# uNavMasterBoard.net
KiCad netlist of a schematic drawn in EAGLE
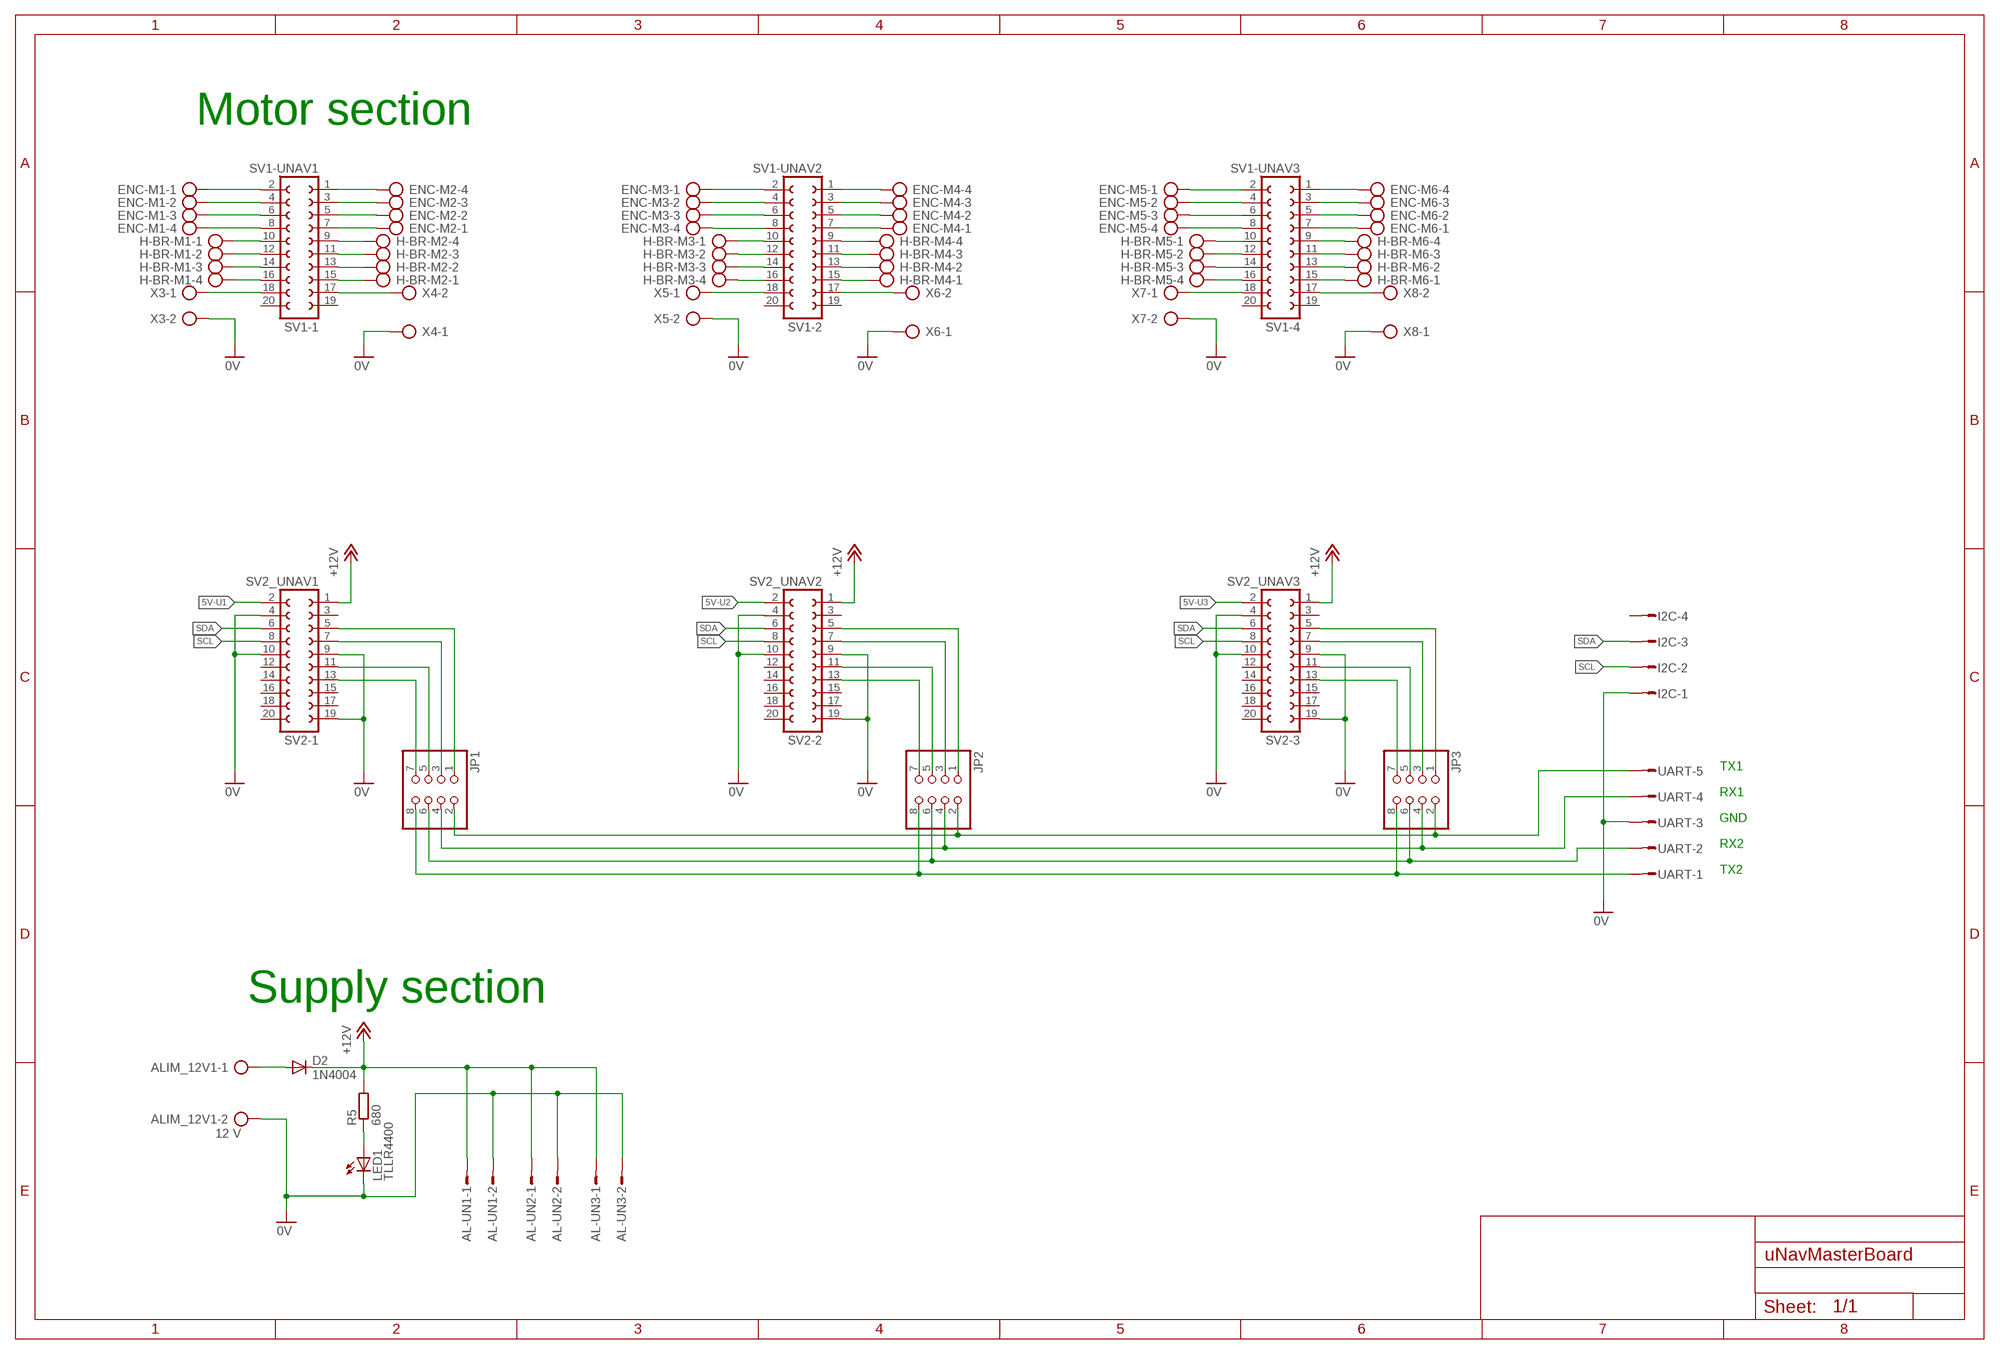
[diagram p0: schematic, sheet 1]

(export (version "E")
  (design (tool "Eeschema 10.0.6"))
  (components
    (comp (ref "AL-UN1")
      (value "S02P")
      (footprint "eagle-import:S02P")
      (fields (field (name "OC_FARNELL") "unknown") (field (name "OC_NEWARK") "unknown"))
      (libsource (lib "eagle-import") (part "S02P"))
    )
    (comp (ref "AL-UN2")
      (value "S02P")
      (footprint "eagle-import:S02P")
      (fields (field (name "OC_FARNELL") "unknown") (field (name "OC_NEWARK") "unknown"))
      (libsource (lib "eagle-import") (part "S02P"))
    )
    (comp (ref "AL-UN3")
      (value "S02P")
      (footprint "eagle-import:S02P")
      (fields (field (name "OC_FARNELL") "unknown") (field (name "OC_NEWARK") "unknown"))
      (libsource (lib "eagle-import") (part "S02P"))
    )
    (comp (ref "ALIM_12V1")
      (value "12 V")
      (footprint "eagle-import:AK500_2")
      (fields (field (name "OC_FARNELL") "unknown") (field (name "OC_NEWARK") "unknown"))
      (libsource (lib "eagle-import") (part "AK500/2"))
    )
    (comp (ref "D2")
      (value "1N4004")
      (footprint "eagle-import:DO41-10")
      (libsource (lib "eagle-import") (part "1N4004"))
    )
    (comp (ref "ENC-M1")
      (value "AK500/4")
      (footprint "eagle-import:AK500_4")
      (libsource (lib "eagle-import") (part "AK500/4"))
    )
    (comp (ref "ENC-M2")
      (value "AK500/4")
      (footprint "eagle-import:AK500_4")
      (libsource (lib "eagle-import") (part "AK500/4"))
    )
    (comp (ref "ENC-M3")
      (value "AK500/4")
      (footprint "eagle-import:AK500_4")
      (libsource (lib "eagle-import") (part "AK500/4"))
    )
    (comp (ref "ENC-M4")
      (value "AK500/4")
      (footprint "eagle-import:AK500_4")
      (libsource (lib "eagle-import") (part "AK500/4"))
    )
    (comp (ref "ENC-M5")
      (value "AK500/4")
      (footprint "eagle-import:AK500_4")
      (libsource (lib "eagle-import") (part "AK500/4"))
    )
    (comp (ref "ENC-M6")
      (value "AK500/4")
      (footprint "eagle-import:AK500_4")
      (libsource (lib "eagle-import") (part "AK500/4"))
    )
    (comp (ref "H-BR-M1")
      (value "AK500/4")
      (footprint "eagle-import:AK500_4")
      (libsource (lib "eagle-import") (part "AK500/4"))
    )
    (comp (ref "H-BR-M2")
      (value "AK500/4")
      (footprint "eagle-import:AK500_4")
      (libsource (lib "eagle-import") (part "AK500/4"))
    )
    (comp (ref "H-BR-M3")
      (value "AK500/4")
      (footprint "eagle-import:AK500_4")
      (libsource (lib "eagle-import") (part "AK500/4"))
    )
    (comp (ref "H-BR-M4")
      (value "AK500/4")
      (footprint "eagle-import:AK500_4")
      (libsource (lib "eagle-import") (part "AK500/4"))
    )
    (comp (ref "H-BR-M5")
      (value "AK500/4")
      (footprint "eagle-import:AK500_4")
      (libsource (lib "eagle-import") (part "AK500/4"))
    )
    (comp (ref "H-BR-M6")
      (value "AK500/4")
      (footprint "eagle-import:AK500_4")
      (libsource (lib "eagle-import") (part "AK500/4"))
    )
    (comp (ref "I2C")
      (value "S04P")
      (footprint "eagle-import:S04P")
      (libsource (lib "eagle-import") (part "S04P"))
    )
    (comp (ref "JP1")
      (value "PINHD-2X4")
      (footprint "eagle-import:2X04")
      (libsource (lib "eagle-import") (part "PINHD-2X4"))
    )
    (comp (ref "JP2")
      (value "PINHD-2X4")
      (footprint "eagle-import:2X04")
      (libsource (lib "eagle-import") (part "PINHD-2X4"))
    )
    (comp (ref "JP3")
      (value "PINHD-2X4")
      (footprint "eagle-import:2X04")
      (libsource (lib "eagle-import") (part "PINHD-2X4"))
    )
    (comp (ref "LED1")
      (value "TLLR4400")
      (footprint "eagle-import:LED3MM")
      (fields
        (field (name "MF") "VISHAY SEMICONDUCTOR")
        (field (name "MF_1") "VISHAY SEMICONDUCTOR")
        (field (name "OC_FARNELL") "1612437")
      )
      (libsource (lib "eagle-import") (part "TLLR4400"))
    )
    (comp (ref "R5")
      (value "680")
      (footprint "eagle-import:0207_10")
      (libsource (lib "eagle-import") (part "R-EU_0207/10"))
    )
    (comp (ref "SV1-1")
      (value "SV1-UNAV1")
      (footprint "eagle-import:FE10-2")
      (fields (field (name "OC_FARNELL") "unknown") (field (name "OC_NEWARK") "unknown"))
      (libsource (lib "eagle-import") (part "FE10-2"))
    )
    (comp (ref "SV1-2")
      (value "SV1-UNAV2")
      (footprint "eagle-import:FE10-2")
      (fields (field (name "OC_FARNELL") "unknown") (field (name "OC_NEWARK") "unknown"))
      (libsource (lib "eagle-import") (part "FE10-2"))
    )
    (comp (ref "SV1-4")
      (value "SV1-UNAV3")
      (footprint "eagle-import:FE10-2")
      (fields (field (name "OC_FARNELL") "unknown") (field (name "OC_NEWARK") "unknown"))
      (libsource (lib "eagle-import") (part "FE10-2"))
    )
    (comp (ref "SV2-1")
      (value "SV2_UNAV1")
      (footprint "eagle-import:FE10-2")
      (fields (field (name "OC_FARNELL") "unknown") (field (name "OC_NEWARK") "unknown"))
      (libsource (lib "eagle-import") (part "FE10-2"))
    )
    (comp (ref "SV2-2")
      (value "SV2_UNAV2")
      (footprint "eagle-import:FE10-2")
      (fields (field (name "OC_FARNELL") "unknown") (field (name "OC_NEWARK") "unknown"))
      (libsource (lib "eagle-import") (part "FE10-2"))
    )
    (comp (ref "SV2-3")
      (value "SV2_UNAV3")
      (footprint "eagle-import:FE10-2")
      (fields (field (name "OC_FARNELL") "unknown") (field (name "OC_NEWARK") "unknown"))
      (libsource (lib "eagle-import") (part "FE10-2"))
    )
    (comp (ref "UART")
      (value "S05P")
      (footprint "eagle-import:S05P")
      (libsource (lib "eagle-import") (part "S05P"))
    )
    (comp (ref "X3")
      (value "AK500/2")
      (footprint "eagle-import:AK500_2")
      (libsource (lib "eagle-import") (part "AK500/2"))
    )
    (comp (ref "X4")
      (value "AK500/2")
      (footprint "eagle-import:AK500_2")
      (libsource (lib "eagle-import") (part "AK500/2"))
    )
    (comp (ref "X5")
      (value "AK500/2")
      (footprint "eagle-import:AK500_2")
      (libsource (lib "eagle-import") (part "AK500/2"))
    )
    (comp (ref "X6")
      (value "AK500/2")
      (footprint "eagle-import:AK500_2")
      (libsource (lib "eagle-import") (part "AK500/2"))
    )
    (comp (ref "X7")
      (value "AK500/2")
      (footprint "eagle-import:AK500_2")
      (libsource (lib "eagle-import") (part "AK500/2"))
    )
    (comp (ref "X8")
      (value "AK500/2")
      (footprint "eagle-import:AK500_2")
      (libsource (lib "eagle-import") (part "AK500/2"))
    )
  )
  (nets
    (net (code "1") (name "+12V") (class "Default")
      (node (ref "AL-UN1") (pin "1") (pinfunction "S_1") (pintype "passive"))
      (node (ref "AL-UN2") (pin "1") (pinfunction "S_1") (pintype "passive"))
      (node (ref "AL-UN3") (pin "1") (pinfunction "S_1") (pintype "passive"))
      (node (ref "D2") (pin "C") (pinfunction "C_C") (pintype "passive"))
      (node (ref "R5") (pin "2") (pinfunction "2_2") (pintype "passive"))
      (node (ref "SV2-1") (pin "1") (pinfunction "1_1") (pintype "passive"))
      (node (ref "SV2-2") (pin "1") (pinfunction "1_1") (pintype "passive"))
      (node (ref "SV2-3") (pin "1") (pinfunction "1_1") (pintype "passive"))
    )
    (net (code "2") (name "0V") (class "Default")
      (node (ref "AL-UN1") (pin "2") (pinfunction "S_2") (pintype "passive"))
      (node (ref "AL-UN2") (pin "2") (pinfunction "S_2") (pintype "passive"))
      (node (ref "AL-UN3") (pin "2") (pinfunction "S_2") (pintype "passive"))
      (node (ref "ALIM_12V1") (pin "2") (pinfunction "KL_2") (pintype "passive"))
      (node (ref "I2C") (pin "1") (pinfunction "S_1") (pintype "passive"))
      (node (ref "LED1") (pin "K") (pinfunction "C_K") (pintype "passive"))
      (node (ref "SV2-1") (pin "10") (pinfunction "10_10") (pintype "passive"))
      (node (ref "SV2-1") (pin "19") (pinfunction "19_19") (pintype "passive"))
      (node (ref "SV2-1") (pin "4") (pinfunction "4_4") (pintype "passive"))
      (node (ref "SV2-1") (pin "9") (pinfunction "9_9") (pintype "passive"))
      (node (ref "SV2-2") (pin "10") (pinfunction "10_10") (pintype "passive"))
      (node (ref "SV2-2") (pin "19") (pinfunction "19_19") (pintype "passive"))
      (node (ref "SV2-2") (pin "4") (pinfunction "4_4") (pintype "passive"))
      (node (ref "SV2-2") (pin "9") (pinfunction "9_9") (pintype "passive"))
      (node (ref "SV2-3") (pin "10") (pinfunction "10_10") (pintype "passive"))
      (node (ref "SV2-3") (pin "19") (pinfunction "19_19") (pintype "passive"))
      (node (ref "SV2-3") (pin "4") (pinfunction "4_4") (pintype "passive"))
      (node (ref "SV2-3") (pin "9") (pinfunction "9_9") (pintype "passive"))
      (node (ref "UART") (pin "3") (pinfunction "S_3") (pintype "passive"))
      (node (ref "X3") (pin "2") (pinfunction "KL_2") (pintype "passive"))
      (node (ref "X4") (pin "1") (pinfunction "KL_1") (pintype "passive"))
      (node (ref "X5") (pin "2") (pinfunction "KL_2") (pintype "passive"))
      (node (ref "X6") (pin "1") (pinfunction "KL_1") (pintype "passive"))
      (node (ref "X7") (pin "2") (pinfunction "KL_2") (pintype "passive"))
      (node (ref "X8") (pin "1") (pinfunction "KL_1") (pintype "passive"))
    )
    (net (code "3") (name "5V-U1") (class "Default")
      (node (ref "SV2-1") (pin "2") (pinfunction "2_2") (pintype "passive"))
    )
    (net (code "4") (name "5V-U2") (class "Default")
      (node (ref "SV2-2") (pin "2") (pinfunction "2_2") (pintype "passive"))
    )
    (net (code "5") (name "5V-U3") (class "Default")
      (node (ref "SV2-3") (pin "2") (pinfunction "2_2") (pintype "passive"))
    )
    (net (code "6") (name "Net-(ALIM_12V1A-KL)") (class "Default")
      (node (ref "ALIM_12V1") (pin "1") (pinfunction "KL_1") (pintype "passive"))
      (node (ref "D2") (pin "A") (pinfunction "A_A") (pintype "passive"))
    )
    (net (code "7") (name "Net-(ENC-M1A-KL)") (class "Default")
      (node (ref "ENC-M1") (pin "1") (pinfunction "KL_1") (pintype "passive"))
      (node (ref "SV1-1") (pin "2") (pinfunction "2_2") (pintype "passive"))
    )
    (net (code "8") (name "Net-(ENC-M1B-KL)") (class "Default")
      (node (ref "ENC-M1") (pin "2") (pinfunction "KL_2") (pintype "passive"))
      (node (ref "SV1-1") (pin "4") (pinfunction "4_4") (pintype "passive"))
    )
    (net (code "9") (name "Net-(ENC-M1C-KL)") (class "Default")
      (node (ref "ENC-M1") (pin "3") (pinfunction "KL_3") (pintype "passive"))
      (node (ref "SV1-1") (pin "6") (pinfunction "6_6") (pintype "passive"))
    )
    (net (code "10") (name "Net-(ENC-M1D-KL)") (class "Default")
      (node (ref "ENC-M1") (pin "4") (pinfunction "KL_4") (pintype "passive"))
      (node (ref "SV1-1") (pin "8") (pinfunction "8_8") (pintype "passive"))
    )
    (net (code "11") (name "Net-(ENC-M2A-KL)") (class "Default")
      (node (ref "ENC-M2") (pin "1") (pinfunction "KL_1") (pintype "passive"))
      (node (ref "SV1-1") (pin "7") (pinfunction "7_7") (pintype "passive"))
    )
    (net (code "12") (name "Net-(ENC-M2B-KL)") (class "Default")
      (node (ref "ENC-M2") (pin "2") (pinfunction "KL_2") (pintype "passive"))
      (node (ref "SV1-1") (pin "5") (pinfunction "5_5") (pintype "passive"))
    )
    (net (code "13") (name "Net-(ENC-M2C-KL)") (class "Default")
      (node (ref "ENC-M2") (pin "3") (pinfunction "KL_3") (pintype "passive"))
      (node (ref "SV1-1") (pin "3") (pinfunction "3_3") (pintype "passive"))
    )
    (net (code "14") (name "Net-(ENC-M2D-KL)") (class "Default")
      (node (ref "ENC-M2") (pin "4") (pinfunction "KL_4") (pintype "passive"))
      (node (ref "SV1-1") (pin "1") (pinfunction "1_1") (pintype "passive"))
    )
    (net (code "15") (name "Net-(ENC-M3A-KL)") (class "Default")
      (node (ref "ENC-M3") (pin "1") (pinfunction "KL_1") (pintype "passive"))
      (node (ref "SV1-2") (pin "2") (pinfunction "2_2") (pintype "passive"))
    )
    (net (code "16") (name "Net-(ENC-M3B-KL)") (class "Default")
      (node (ref "ENC-M3") (pin "2") (pinfunction "KL_2") (pintype "passive"))
      (node (ref "SV1-2") (pin "4") (pinfunction "4_4") (pintype "passive"))
    )
    (net (code "17") (name "Net-(ENC-M3C-KL)") (class "Default")
      (node (ref "ENC-M3") (pin "3") (pinfunction "KL_3") (pintype "passive"))
      (node (ref "SV1-2") (pin "6") (pinfunction "6_6") (pintype "passive"))
    )
    (net (code "18") (name "Net-(ENC-M3D-KL)") (class "Default")
      (node (ref "ENC-M3") (pin "4") (pinfunction "KL_4") (pintype "passive"))
      (node (ref "SV1-2") (pin "8") (pinfunction "8_8") (pintype "passive"))
    )
    (net (code "19") (name "Net-(ENC-M4A-KL)") (class "Default")
      (node (ref "ENC-M4") (pin "1") (pinfunction "KL_1") (pintype "passive"))
      (node (ref "SV1-2") (pin "7") (pinfunction "7_7") (pintype "passive"))
    )
    (net (code "20") (name "Net-(ENC-M4B-KL)") (class "Default")
      (node (ref "ENC-M4") (pin "2") (pinfunction "KL_2") (pintype "passive"))
      (node (ref "SV1-2") (pin "5") (pinfunction "5_5") (pintype "passive"))
    )
    (net (code "21") (name "Net-(ENC-M4C-KL)") (class "Default")
      (node (ref "ENC-M4") (pin "3") (pinfunction "KL_3") (pintype "passive"))
      (node (ref "SV1-2") (pin "3") (pinfunction "3_3") (pintype "passive"))
    )
    (net (code "22") (name "Net-(ENC-M4D-KL)") (class "Default")
      (node (ref "ENC-M4") (pin "4") (pinfunction "KL_4") (pintype "passive"))
      (node (ref "SV1-2") (pin "1") (pinfunction "1_1") (pintype "passive"))
    )
    (net (code "23") (name "Net-(ENC-M5A-KL)") (class "Default")
      (node (ref "ENC-M5") (pin "1") (pinfunction "KL_1") (pintype "passive"))
      (node (ref "SV1-4") (pin "2") (pinfunction "2_2") (pintype "passive"))
    )
    (net (code "24") (name "Net-(ENC-M5B-KL)") (class "Default")
      (node (ref "ENC-M5") (pin "2") (pinfunction "KL_2") (pintype "passive"))
      (node (ref "SV1-4") (pin "4") (pinfunction "4_4") (pintype "passive"))
    )
    (net (code "25") (name "Net-(ENC-M5C-KL)") (class "Default")
      (node (ref "ENC-M5") (pin "3") (pinfunction "KL_3") (pintype "passive"))
      (node (ref "SV1-4") (pin "6") (pinfunction "6_6") (pintype "passive"))
    )
    (net (code "26") (name "Net-(ENC-M5D-KL)") (class "Default")
      (node (ref "ENC-M5") (pin "4") (pinfunction "KL_4") (pintype "passive"))
      (node (ref "SV1-4") (pin "8") (pinfunction "8_8") (pintype "passive"))
    )
    (net (code "27") (name "Net-(ENC-M6A-KL)") (class "Default")
      (node (ref "ENC-M6") (pin "1") (pinfunction "KL_1") (pintype "passive"))
      (node (ref "SV1-4") (pin "7") (pinfunction "7_7") (pintype "passive"))
    )
    (net (code "28") (name "Net-(ENC-M6B-KL)") (class "Default")
      (node (ref "ENC-M6") (pin "2") (pinfunction "KL_2") (pintype "passive"))
      (node (ref "SV1-4") (pin "5") (pinfunction "5_5") (pintype "passive"))
    )
    (net (code "29") (name "Net-(ENC-M6C-KL)") (class "Default")
      (node (ref "ENC-M6") (pin "3") (pinfunction "KL_3") (pintype "passive"))
      (node (ref "SV1-4") (pin "3") (pinfunction "3_3") (pintype "passive"))
    )
    (net (code "30") (name "Net-(ENC-M6D-KL)") (class "Default")
      (node (ref "ENC-M6") (pin "4") (pinfunction "KL_4") (pintype "passive"))
      (node (ref "SV1-4") (pin "1") (pinfunction "1_1") (pintype "passive"))
    )
    (net (code "31") (name "Net-(H-BR-M1A-KL)") (class "Default")
      (node (ref "H-BR-M1") (pin "1") (pinfunction "KL_1") (pintype "passive"))
      (node (ref "SV1-1") (pin "10") (pinfunction "10_10") (pintype "passive"))
    )
    (net (code "32") (name "Net-(H-BR-M1B-KL)") (class "Default")
      (node (ref "H-BR-M1") (pin "2") (pinfunction "KL_2") (pintype "passive"))
      (node (ref "SV1-1") (pin "12") (pinfunction "12_12") (pintype "passive"))
    )
    (net (code "33") (name "Net-(H-BR-M1C-KL)") (class "Default")
      (node (ref "H-BR-M1") (pin "3") (pinfunction "KL_3") (pintype "passive"))
      (node (ref "SV1-1") (pin "14") (pinfunction "14_14") (pintype "passive"))
    )
    (net (code "34") (name "Net-(H-BR-M1D-KL)") (class "Default")
      (node (ref "H-BR-M1") (pin "4") (pinfunction "KL_4") (pintype "passive"))
      (node (ref "SV1-1") (pin "16") (pinfunction "16_16") (pintype "passive"))
    )
    (net (code "35") (name "Net-(H-BR-M2A-KL)") (class "Default")
      (node (ref "H-BR-M2") (pin "1") (pinfunction "KL_1") (pintype "passive"))
      (node (ref "SV1-1") (pin "15") (pinfunction "15_15") (pintype "passive"))
    )
    (net (code "36") (name "Net-(H-BR-M2B-KL)") (class "Default")
      (node (ref "H-BR-M2") (pin "2") (pinfunction "KL_2") (pintype "passive"))
      (node (ref "SV1-1") (pin "13") (pinfunction "13_13") (pintype "passive"))
    )
    (net (code "37") (name "Net-(H-BR-M2C-KL)") (class "Default")
      (node (ref "H-BR-M2") (pin "3") (pinfunction "KL_3") (pintype "passive"))
      (node (ref "SV1-1") (pin "11") (pinfunction "11_11") (pintype "passive"))
    )
    (net (code "38") (name "Net-(H-BR-M2D-KL)") (class "Default")
      (node (ref "H-BR-M2") (pin "4") (pinfunction "KL_4") (pintype "passive"))
      (node (ref "SV1-1") (pin "9") (pinfunction "9_9") (pintype "passive"))
    )
    (net (code "39") (name "Net-(H-BR-M3A-KL)") (class "Default")
      (node (ref "H-BR-M3") (pin "1") (pinfunction "KL_1") (pintype "passive"))
      (node (ref "SV1-2") (pin "10") (pinfunction "10_10") (pintype "passive"))
    )
    (net (code "40") (name "Net-(H-BR-M3B-KL)") (class "Default")
      (node (ref "H-BR-M3") (pin "2") (pinfunction "KL_2") (pintype "passive"))
      (node (ref "SV1-2") (pin "12") (pinfunction "12_12") (pintype "passive"))
    )
    (net (code "41") (name "Net-(H-BR-M3C-KL)") (class "Default")
      (node (ref "H-BR-M3") (pin "3") (pinfunction "KL_3") (pintype "passive"))
      (node (ref "SV1-2") (pin "14") (pinfunction "14_14") (pintype "passive"))
    )
    (net (code "42") (name "Net-(H-BR-M3D-KL)") (class "Default")
      (node (ref "H-BR-M3") (pin "4") (pinfunction "KL_4") (pintype "passive"))
      (node (ref "SV1-2") (pin "16") (pinfunction "16_16") (pintype "passive"))
    )
    (net (code "43") (name "Net-(H-BR-M4A-KL)") (class "Default")
      (node (ref "H-BR-M4") (pin "1") (pinfunction "KL_1") (pintype "passive"))
      (node (ref "SV1-2") (pin "15") (pinfunction "15_15") (pintype "passive"))
    )
    (net (code "44") (name "Net-(H-BR-M4B-KL)") (class "Default")
      (node (ref "H-BR-M4") (pin "2") (pinfunction "KL_2") (pintype "passive"))
      (node (ref "SV1-2") (pin "13") (pinfunction "13_13") (pintype "passive"))
    )
    (net (code "45") (name "Net-(H-BR-M4C-KL)") (class "Default")
      (node (ref "H-BR-M4") (pin "3") (pinfunction "KL_3") (pintype "passive"))
      (node (ref "SV1-2") (pin "11") (pinfunction "11_11") (pintype "passive"))
    )
    (net (code "46") (name "Net-(H-BR-M4D-KL)") (class "Default")
      (node (ref "H-BR-M4") (pin "4") (pinfunction "KL_4") (pintype "passive"))
      (node (ref "SV1-2") (pin "9") (pinfunction "9_9") (pintype "passive"))
    )
    (net (code "47") (name "Net-(H-BR-M5A-KL)") (class "Default")
      (node (ref "H-BR-M5") (pin "1") (pinfunction "KL_1") (pintype "passive"))
      (node (ref "SV1-4") (pin "10") (pinfunction "10_10") (pintype "passive"))
    )
    (net (code "48") (name "Net-(H-BR-M5B-KL)") (class "Default")
      (node (ref "H-BR-M5") (pin "2") (pinfunction "KL_2") (pintype "passive"))
      (node (ref "SV1-4") (pin "12") (pinfunction "12_12") (pintype "passive"))
    )
    (net (code "49") (name "Net-(H-BR-M5C-KL)") (class "Default")
      (node (ref "H-BR-M5") (pin "3") (pinfunction "KL_3") (pintype "passive"))
      (node (ref "SV1-4") (pin "14") (pinfunction "14_14") (pintype "passive"))
    )
    (net (code "50") (name "Net-(H-BR-M5D-KL)") (class "Default")
      (node (ref "H-BR-M5") (pin "4") (pinfunction "KL_4") (pintype "passive"))
      (node (ref "SV1-4") (pin "16") (pinfunction "16_16") (pintype "passive"))
    )
    (net (code "51") (name "Net-(H-BR-M6A-KL)") (class "Default")
      (node (ref "H-BR-M6") (pin "1") (pinfunction "KL_1") (pintype "passive"))
      (node (ref "SV1-4") (pin "15") (pinfunction "15_15") (pintype "passive"))
    )
    (net (code "52") (name "Net-(H-BR-M6B-KL)") (class "Default")
      (node (ref "H-BR-M6") (pin "2") (pinfunction "KL_2") (pintype "passive"))
      (node (ref "SV1-4") (pin "13") (pinfunction "13_13") (pintype "passive"))
    )
    (net (code "53") (name "Net-(H-BR-M6C-KL)") (class "Default")
      (node (ref "H-BR-M6") (pin "3") (pinfunction "KL_3") (pintype "passive"))
      (node (ref "SV1-4") (pin "11") (pinfunction "11_11") (pintype "passive"))
    )
    (net (code "54") (name "Net-(H-BR-M6D-KL)") (class "Default")
      (node (ref "H-BR-M6") (pin "4") (pinfunction "KL_4") (pintype "passive"))
      (node (ref "SV1-4") (pin "9") (pinfunction "9_9") (pintype "passive"))
    )
    (net (code "55") (name "Net-(JP1-Pad1)") (class "Default")
      (node (ref "JP1") (pin "1") (pinfunction "1_1") (pintype "passive"))
      (node (ref "SV2-1") (pin "5") (pinfunction "5_5") (pintype "passive"))
    )
    (net (code "56") (name "Net-(JP1-Pad3)") (class "Default")
      (node (ref "JP1") (pin "3") (pinfunction "3_3") (pintype "passive"))
      (node (ref "SV2-1") (pin "7") (pinfunction "7_7") (pintype "passive"))
    )
    (net (code "57") (name "Net-(JP1-Pad5)") (class "Default")
      (node (ref "JP1") (pin "5") (pinfunction "5_5") (pintype "passive"))
      (node (ref "SV2-1") (pin "11") (pinfunction "11_11") (pintype "passive"))
    )
    (net (code "58") (name "Net-(JP1-Pad7)") (class "Default")
      (node (ref "JP1") (pin "7") (pinfunction "7_7") (pintype "passive"))
      (node (ref "SV2-1") (pin "13") (pinfunction "13_13") (pintype "passive"))
    )
    (net (code "59") (name "Net-(JP2-Pad1)") (class "Default")
      (node (ref "JP2") (pin "1") (pinfunction "1_1") (pintype "passive"))
      (node (ref "SV2-2") (pin "5") (pinfunction "5_5") (pintype "passive"))
    )
    (net (code "60") (name "Net-(JP2-Pad3)") (class "Default")
      (node (ref "JP2") (pin "3") (pinfunction "3_3") (pintype "passive"))
      (node (ref "SV2-2") (pin "7") (pinfunction "7_7") (pintype "passive"))
    )
    (net (code "61") (name "Net-(JP2-Pad5)") (class "Default")
      (node (ref "JP2") (pin "5") (pinfunction "5_5") (pintype "passive"))
      (node (ref "SV2-2") (pin "11") (pinfunction "11_11") (pintype "passive"))
    )
    (net (code "62") (name "Net-(JP2-Pad7)") (class "Default")
      (node (ref "JP2") (pin "7") (pinfunction "7_7") (pintype "passive"))
      (node (ref "SV2-2") (pin "13") (pinfunction "13_13") (pintype "passive"))
    )
    (net (code "63") (name "Net-(JP3-Pad1)") (class "Default")
      (node (ref "JP3") (pin "1") (pinfunction "1_1") (pintype "passive"))
      (node (ref "SV2-3") (pin "5") (pinfunction "5_5") (pintype "passive"))
    )
    (net (code "64") (name "Net-(JP3-Pad3)") (class "Default")
      (node (ref "JP3") (pin "3") (pinfunction "3_3") (pintype "passive"))
      (node (ref "SV2-3") (pin "7") (pinfunction "7_7") (pintype "passive"))
    )
    (net (code "65") (name "Net-(JP3-Pad5)") (class "Default")
      (node (ref "JP3") (pin "5") (pinfunction "5_5") (pintype "passive"))
      (node (ref "SV2-3") (pin "11") (pinfunction "11_11") (pintype "passive"))
    )
    (net (code "66") (name "Net-(JP3-Pad7)") (class "Default")
      (node (ref "JP3") (pin "7") (pinfunction "7_7") (pintype "passive"))
      (node (ref "SV2-3") (pin "13") (pinfunction "13_13") (pintype "passive"))
    )
    (net (code "67") (name "Net-(LED1-PadA)") (class "Default")
      (node (ref "LED1") (pin "A") (pinfunction "A_A") (pintype "passive"))
      (node (ref "R5") (pin "1") (pinfunction "1_1") (pintype "passive"))
    )
    (net (code "68") (name "Net-(UARTA-S)") (class "Default")
      (node (ref "JP1") (pin "8") (pinfunction "8_8") (pintype "passive"))
      (node (ref "JP2") (pin "8") (pinfunction "8_8") (pintype "passive"))
      (node (ref "JP3") (pin "8") (pinfunction "8_8") (pintype "passive"))
      (node (ref "UART") (pin "1") (pinfunction "S_1") (pintype "passive"))
    )
    (net (code "69") (name "Net-(UARTB-S)") (class "Default")
      (node (ref "JP1") (pin "6") (pinfunction "6_6") (pintype "passive"))
      (node (ref "JP2") (pin "6") (pinfunction "6_6") (pintype "passive"))
      (node (ref "JP3") (pin "6") (pinfunction "6_6") (pintype "passive"))
      (node (ref "UART") (pin "2") (pinfunction "S_2") (pintype "passive"))
    )
    (net (code "70") (name "Net-(UARTD-S)") (class "Default")
      (node (ref "JP1") (pin "4") (pinfunction "4_4") (pintype "passive"))
      (node (ref "JP2") (pin "4") (pinfunction "4_4") (pintype "passive"))
      (node (ref "JP3") (pin "4") (pinfunction "4_4") (pintype "passive"))
      (node (ref "UART") (pin "4") (pinfunction "S_4") (pintype "passive"))
    )
    (net (code "71") (name "Net-(UARTE-S)") (class "Default")
      (node (ref "JP1") (pin "2") (pinfunction "2_2") (pintype "passive"))
      (node (ref "JP2") (pin "2") (pinfunction "2_2") (pintype "passive"))
      (node (ref "JP3") (pin "2") (pinfunction "2_2") (pintype "passive"))
      (node (ref "UART") (pin "5") (pinfunction "S_5") (pintype "passive"))
    )
    (net (code "72") (name "Net-(X3A-KL)") (class "Default")
      (node (ref "SV1-1") (pin "18") (pinfunction "18_18") (pintype "passive"))
      (node (ref "X3") (pin "1") (pinfunction "KL_1") (pintype "passive"))
    )
    (net (code "73") (name "Net-(X4B-KL)") (class "Default")
      (node (ref "SV1-1") (pin "17") (pinfunction "17_17") (pintype "passive"))
      (node (ref "X4") (pin "2") (pinfunction "KL_2") (pintype "passive"))
    )
    (net (code "74") (name "Net-(X5A-KL)") (class "Default")
      (node (ref "SV1-2") (pin "18") (pinfunction "18_18") (pintype "passive"))
      (node (ref "X5") (pin "1") (pinfunction "KL_1") (pintype "passive"))
    )
    (net (code "75") (name "Net-(X6B-KL)") (class "Default")
      (node (ref "SV1-2") (pin "17") (pinfunction "17_17") (pintype "passive"))
      (node (ref "X6") (pin "2") (pinfunction "KL_2") (pintype "passive"))
    )
    (net (code "76") (name "Net-(X7A-KL)") (class "Default")
      (node (ref "SV1-4") (pin "18") (pinfunction "18_18") (pintype "passive"))
      (node (ref "X7") (pin "1") (pinfunction "KL_1") (pintype "passive"))
    )
    (net (code "77") (name "Net-(X8B-KL)") (class "Default")
      (node (ref "SV1-4") (pin "17") (pinfunction "17_17") (pintype "passive"))
      (node (ref "X8") (pin "2") (pinfunction "KL_2") (pintype "passive"))
    )
    (net (code "78") (name "SCL") (class "Default")
      (node (ref "I2C") (pin "2") (pinfunction "S_2") (pintype "passive"))
      (node (ref "SV2-1") (pin "8") (pinfunction "8_8") (pintype "passive"))
      (node (ref "SV2-2") (pin "8") (pinfunction "8_8") (pintype "passive"))
      (node (ref "SV2-3") (pin "8") (pinfunction "8_8") (pintype "passive"))
    )
    (net (code "79") (name "SDA") (class "Default")
      (node (ref "I2C") (pin "3") (pinfunction "S_3") (pintype "passive"))
      (node (ref "SV2-1") (pin "6") (pinfunction "6_6") (pintype "passive"))
      (node (ref "SV2-2") (pin "6") (pinfunction "6_6") (pintype "passive"))
      (node (ref "SV2-3") (pin "6") (pinfunction "6_6") (pintype "passive"))
    )
    (net (code "80") (name "unconnected-(I2CD-S-Pad4)") (class "Default")
      (node (ref "I2C") (pin "4") (pinfunction "S_4") (pintype "passive"))
    )
    (net (code "81") (name "unconnected-(SV1-1-Pad19)") (class "Default")
      (node (ref "SV1-1") (pin "19") (pinfunction "19_19") (pintype "passive"))
    )
    (net (code "82") (name "unconnected-(SV1-1-Pad20)") (class "Default")
      (node (ref "SV1-1") (pin "20") (pinfunction "20_20") (pintype "passive"))
    )
    (net (code "83") (name "unconnected-(SV1-2-Pad19)") (class "Default")
      (node (ref "SV1-2") (pin "19") (pinfunction "19_19") (pintype "passive"))
    )
    (net (code "84") (name "unconnected-(SV1-2-Pad20)") (class "Default")
      (node (ref "SV1-2") (pin "20") (pinfunction "20_20") (pintype "passive"))
    )
    (net (code "85") (name "unconnected-(SV1-4-Pad19)") (class "Default")
      (node (ref "SV1-4") (pin "19") (pinfunction "19_19") (pintype "passive"))
    )
    (net (code "86") (name "unconnected-(SV1-4-Pad20)") (class "Default")
      (node (ref "SV1-4") (pin "20") (pinfunction "20_20") (pintype "passive"))
    )
    (net (code "87") (name "unconnected-(SV2-1-Pad3)") (class "Default")
      (node (ref "SV2-1") (pin "3") (pinfunction "3_3") (pintype "passive"))
    )
    (net (code "88") (name "unconnected-(SV2-1-Pad12)") (class "Default")
      (node (ref "SV2-1") (pin "12") (pinfunction "12_12") (pintype "passive"))
    )
    (net (code "89") (name "unconnected-(SV2-1-Pad14)") (class "Default")
      (node (ref "SV2-1") (pin "14") (pinfunction "14_14") (pintype "passive"))
    )
    (net (code "90") (name "unconnected-(SV2-1-Pad15)") (class "Default")
      (node (ref "SV2-1") (pin "15") (pinfunction "15_15") (pintype "passive"))
    )
    (net (code "91") (name "unconnected-(SV2-1-Pad16)") (class "Default")
      (node (ref "SV2-1") (pin "16") (pinfunction "16_16") (pintype "passive"))
    )
    (net (code "92") (name "unconnected-(SV2-1-Pad17)") (class "Default")
      (node (ref "SV2-1") (pin "17") (pinfunction "17_17") (pintype "passive"))
    )
    (net (code "93") (name "unconnected-(SV2-1-Pad18)") (class "Default")
      (node (ref "SV2-1") (pin "18") (pinfunction "18_18") (pintype "passive"))
    )
    (net (code "94") (name "unconnected-(SV2-1-Pad20)") (class "Default")
      (node (ref "SV2-1") (pin "20") (pinfunction "20_20") (pintype "passive"))
    )
    (net (code "95") (name "unconnected-(SV2-2-Pad3)") (class "Default")
      (node (ref "SV2-2") (pin "3") (pinfunction "3_3") (pintype "passive"))
    )
    (net (code "96") (name "unconnected-(SV2-2-Pad12)") (class "Default")
      (node (ref "SV2-2") (pin "12") (pinfunction "12_12") (pintype "passive"))
    )
    (net (code "97") (name "unconnected-(SV2-2-Pad14)") (class "Default")
      (node (ref "SV2-2") (pin "14") (pinfunction "14_14") (pintype "passive"))
    )
    (net (code "98") (name "unconnected-(SV2-2-Pad15)") (class "Default")
      (node (ref "SV2-2") (pin "15") (pinfunction "15_15") (pintype "passive"))
    )
    (net (code "99") (name "unconnected-(SV2-2-Pad16)") (class "Default")
      (node (ref "SV2-2") (pin "16") (pinfunction "16_16") (pintype "passive"))
    )
    (net (code "100") (name "unconnected-(SV2-2-Pad17)") (class "Default")
      (node (ref "SV2-2") (pin "17") (pinfunction "17_17") (pintype "passive"))
    )
    (net (code "101") (name "unconnected-(SV2-2-Pad18)") (class "Default")
      (node (ref "SV2-2") (pin "18") (pinfunction "18_18") (pintype "passive"))
    )
    (net (code "102") (name "unconnected-(SV2-2-Pad20)") (class "Default")
      (node (ref "SV2-2") (pin "20") (pinfunction "20_20") (pintype "passive"))
    )
    (net (code "103") (name "unconnected-(SV2-3-Pad3)") (class "Default")
      (node (ref "SV2-3") (pin "3") (pinfunction "3_3") (pintype "passive"))
    )
    (net (code "104") (name "unconnected-(SV2-3-Pad12)") (class "Default")
      (node (ref "SV2-3") (pin "12") (pinfunction "12_12") (pintype "passive"))
    )
    (net (code "105") (name "unconnected-(SV2-3-Pad14)") (class "Default")
      (node (ref "SV2-3") (pin "14") (pinfunction "14_14") (pintype "passive"))
    )
    (net (code "106") (name "unconnected-(SV2-3-Pad15)") (class "Default")
      (node (ref "SV2-3") (pin "15") (pinfunction "15_15") (pintype "passive"))
    )
    (net (code "107") (name "unconnected-(SV2-3-Pad16)") (class "Default")
      (node (ref "SV2-3") (pin "16") (pinfunction "16_16") (pintype "passive"))
    )
    (net (code "108") (name "unconnected-(SV2-3-Pad17)") (class "Default")
      (node (ref "SV2-3") (pin "17") (pinfunction "17_17") (pintype "passive"))
    )
    (net (code "109") (name "unconnected-(SV2-3-Pad18)") (class "Default")
      (node (ref "SV2-3") (pin "18") (pinfunction "18_18") (pintype "passive"))
    )
    (net (code "110") (name "unconnected-(SV2-3-Pad20)") (class "Default")
      (node (ref "SV2-3") (pin "20") (pinfunction "20_20") (pintype "passive"))
    )
  )
)
